# 02_MCU.net
KiCad netlist of a schematic drawn in Altium Designer
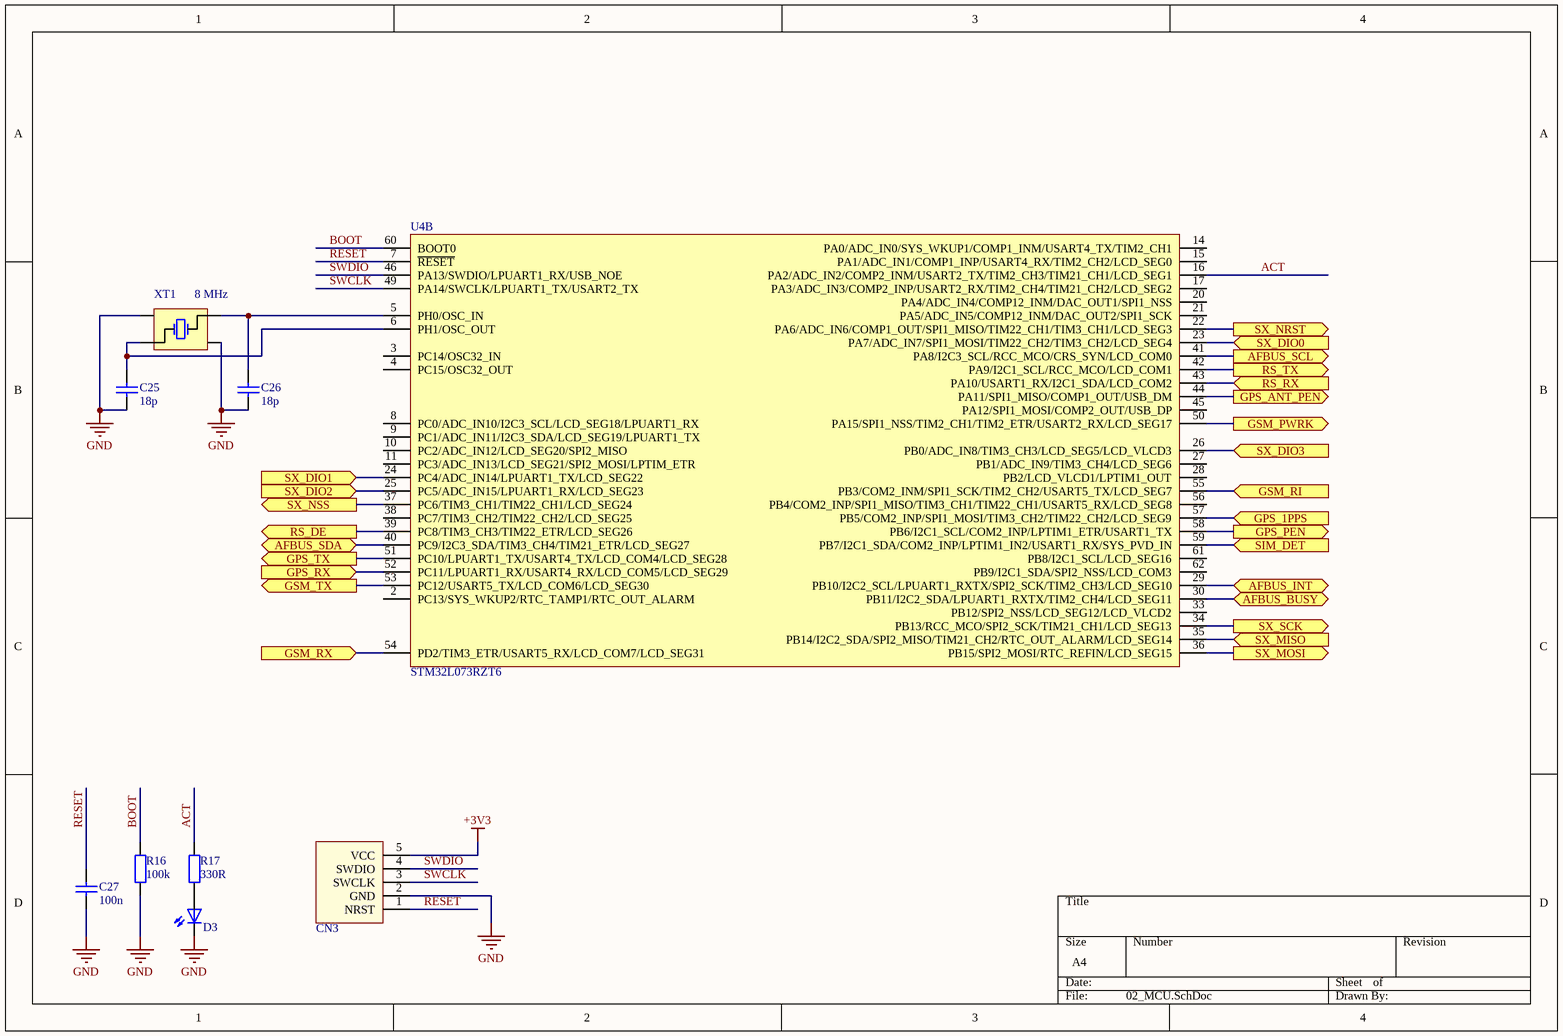
[diagram p0: 02_MCU.SchDoc]

(export (version "E")
  (design (tool "Eeschema 10.0.6"))
  (components
    (comp (ref "C25")
      (value "18p")
      (footprint "C0603_IPC_MD")
      (description "CAP CER 18PF 50V C0G/NP0 0603")
      (fields
        (field (name "MANUFACTURER") "Samsung Electro-Mechanics")
        (field (name "MANUFACTURER PART NUMBER") "CL10C180JB8NNNC")
      )
      (libsource (lib "alfasat_lib") (part "CL10C180JB8NNNC"))
    )
    (comp (ref "C26")
      (value "18p")
      (footprint "C0603_IPC_MD")
      (description "CAP CER 18PF 50V C0G/NP0 0603")
      (fields
        (field (name "MANUFACTURER") "Samsung Electro-Mechanics")
        (field (name "MANUFACTURER PART NUMBER") "CL10C180JB8NNNC")
      )
      (libsource (lib "alfasat_lib") (part "CL10C180JB8NNNC"))
    )
    (comp (ref "C27")
      (value "100n")
      (footprint "C0603_IPC_MD")
      (description "CAP CER 0.1UF 16V X7R 0603")
      (fields
        (field (name "MANUFACTURER") "Samsung Electro-Mechanics")
        (field (name "MANUFACTURER PART NUMBER") "CL10B104KO8WPNC")
      )
      (libsource (lib "alfasat_lib") (part "CL10B104KO8WPNC"))
    )
    (comp (ref "CN3")
      (value "SWD")
      (footprint "SWD_CON_VAR2")
      (description "SWDIO SWCLK VDD GND NRST")
      (libsource (lib "alfasat_parts_lib") (part "SWD-CONNECTOR_VAR1"))
    )
    (comp (ref "D3")
      (value "LTST-C190GKT")
      (footprint "LED_0603")
      (description "LED GREEN CLEAR CHIP SMD 0603")
      (fields (field (name "MANUFACTURER") "Lite-On Inc."))
      (libsource (lib "alfasat_lib") (part "LTST-C190GKT"))
    )
    (comp (ref "R16")
      (value "100k")
      (footprint "R0603_IPC_MD")
      (description "RES 100K OHM 1% 1/10W 0603")
      (fields
        (field (name "MANUFACTURER") "Bourns Inc.")
        (field (name "MANUFACTURER PART NUMBER") "RMCF0603FT100K")
      )
      (libsource (lib "alfasat_lib") (part "RMCF0603FT100K"))
    )
    (comp (ref "R17")
      (value "330R")
      (footprint "R0603_IPC_MD")
      (description "RES SMD 330 OHM 5% 1/10W 0603")
      (fields
        (field (name "MANUFACTURER") "Bourns Inc.")
        (field (name "MANUFACTURER PART NUMBER") "CR0603-JW-331ELF")
      )
      (libsource (lib "alfasat_lib") (part "CR0603-JW-331ELF"))
    )
    (comp (ref "U4")
      (value "STM32L073RZT6")
      (footprint "LQFP64_10X10MM")
      (description "Ultra-low-power 32-bit MCU ARM®-based Cortex®-M0+")
      (fields (field (name "MANUFACTURER") "ST"))
      (libsource (lib "alfasat_lib") (part "STM32L073RZT6"))
    )
    (comp (ref "XT1")
      (value "8 MHz")
      (footprint "5.0X3.2_4PAD_SMT")
      (description "8MHz ±10ppm Crystal 10pF 200 Ohms 4-SMD, No Lead")
      (fields
        (field (name "MANUFACTURER PART NUMBER") "ABM3B-8.000MHZ-10-1-U-T")
        (field (name "MANUFACTURER") "Abracon LLC")
      )
      (libsource (lib "alfasat_lib") (part "ABM3B-8.000MHZ-10-1-U-T"))
    )
  )
  (nets
    (net (code "1") (name "+3V3") (class "Default")
      (node (ref "CN3") (pin "5") (pinfunction "VCC_5") (pintype "passive"))
    )
    (net (code "2") (name "/ACT") (class "Default")
      (node (ref "R17") (pin "1") (pinfunction "1_1") (pintype "passive"))
      (node (ref "U4") (pin "16") (pinfunction "PA2/ADC_IN2/COMP2_INM/USART2_TX/TIM2_CH3/TIM21_CH1/LCD_SEG1_16") (pintype "passive"))
    )
    (net (code "3") (name "/AFBUS_BUSY") (class "Default")
      (node (ref "U4") (pin "30") (pinfunction "PB11/I2C2_SDA/LPUART1_RXTX/TIM2_CH4/LCD_SEG11_30") (pintype "passive"))
    )
    (net (code "4") (name "/AFBUS_INT") (class "Default")
      (node (ref "U4") (pin "29") (pinfunction "PB10/I2C2_SCL/LPUART1_RXTX/SPI2_SCK/TIM2_CH3/LCD_SEG10_29") (pintype "passive"))
    )
    (net (code "5") (name "/AFBUS_SCL") (class "Default")
      (node (ref "U4") (pin "41") (pinfunction "PA8/I2C3_SCL/RCC_MCO/CRS_SYN/LCD_COM0_41") (pintype "passive"))
    )
    (net (code "6") (name "/AFBUS_SDA") (class "Default")
      (node (ref "U4") (pin "40") (pinfunction "PC9/I2C3_SDA/TIM3_CH4/TIM21_ETR/LCD_SEG27_40") (pintype "passive"))
    )
    (net (code "7") (name "/BOOT") (class "Default")
      (node (ref "R16") (pin "2") (pinfunction "2_2") (pintype "passive"))
      (node (ref "U4") (pin "60") (pinfunction "BOOT0_60") (pintype "passive"))
    )
    (net (code "8") (name "/GPS_1PPS") (class "Default")
      (node (ref "U4") (pin "57") (pinfunction "PB5/COM2_INP/SPI1_MOSI/TIM3_CH2/TIM22_CH2/LCD_SEG9_57") (pintype "passive"))
    )
    (net (code "9") (name "/GPS_ANT_PEN") (class "Default")
      (node (ref "U4") (pin "44") (pinfunction "PA11/SPI1_MISO/COMP1_OUT/USB_DM_44") (pintype "passive"))
    )
    (net (code "10") (name "/GPS_PEN") (class "Default")
      (node (ref "U4") (pin "58") (pinfunction "PB6/I2C1_SCL/COM2_INP/LPTIM1_ETR/USART1_TX_58") (pintype "passive"))
    )
    (net (code "11") (name "/GPS_RX") (class "Default")
      (node (ref "U4") (pin "52") (pinfunction "PC11/LPUART1_RX/USART4_RX/LCD_COM5/LCD_SEG29_52") (pintype "passive"))
    )
    (net (code "12") (name "/GPS_TX") (class "Default")
      (node (ref "U4") (pin "51") (pinfunction "PC10/LPUART1_TX/USART4_TX/LCD_COM4/LCD_SEG28_51") (pintype "passive"))
    )
    (net (code "13") (name "/GSM_PWRK") (class "Default")
      (node (ref "U4") (pin "50") (pinfunction "PA15/SPI1_NSS/TIM2_CH1/TIM2_ETR/USART2_RX/LCD_SEG17_50") (pintype "passive"))
    )
    (net (code "14") (name "/GSM_RI") (class "Default")
      (node (ref "U4") (pin "55") (pinfunction "PB3/COM2_INM/SPI1_SCK/TIM2_CH2/USART5_TX/LCD_SEG7_55") (pintype "passive"))
    )
    (net (code "15") (name "/GSM_RX") (class "Default")
      (node (ref "U4") (pin "54") (pinfunction "PD2/TIM3_ETR/USART5_RX/LCD_COM7/LCD_SEG31_54") (pintype "passive"))
    )
    (net (code "16") (name "/GSM_TX") (class "Default")
      (node (ref "U4") (pin "53") (pinfunction "PC12/USART5_TX/LCD_COM6/LCD_SEG30_53") (pintype "passive"))
    )
    (net (code "17") (name "/RESET") (class "Default")
      (node (ref "C27") (pin "2") (pinfunction "2_2") (pintype "passive"))
      (node (ref "CN3") (pin "1") (pinfunction "NRST_1") (pintype "passive"))
      (node (ref "U4") (pin "7") (pinfunction "~{RESET}_7") (pintype "passive"))
    )
    (net (code "18") (name "/RS_DE") (class "Default")
      (node (ref "U4") (pin "39") (pinfunction "PC8/TIM3_CH3/TIM22_ETR/LCD_SEG26_39") (pintype "passive"))
    )
    (net (code "19") (name "/RS_RX") (class "Default")
      (node (ref "U4") (pin "43") (pinfunction "PA10/USART1_RX/I2C1_SDA/LCD_COM2_43") (pintype "passive"))
    )
    (net (code "20") (name "/RS_TX") (class "Default")
      (node (ref "U4") (pin "42") (pinfunction "PA9/I2C1_SCL/RCC_MCO/LCD_COM1_42") (pintype "passive"))
    )
    (net (code "21") (name "/SIM_DET") (class "Default")
      (node (ref "U4") (pin "59") (pinfunction "PB7/I2C1_SDA/COM2_INP/LPTIM1_IN2/USART1_RX/SYS_PVD_IN_59") (pintype "passive"))
    )
    (net (code "22") (name "/SWCLK") (class "Default")
      (node (ref "CN3") (pin "3") (pinfunction "SWCLK_3") (pintype "passive"))
      (node (ref "U4") (pin "49") (pinfunction "PA14/SWCLK/LPUART1_TX/USART2_TX_49") (pintype "passive"))
    )
    (net (code "23") (name "/SWDIO") (class "Default")
      (node (ref "CN3") (pin "4") (pinfunction "SWDIO_4") (pintype "passive"))
      (node (ref "U4") (pin "46") (pinfunction "PA13/SWDIO/LPUART1_RX/USB_NOE_46") (pintype "passive"))
    )
    (net (code "24") (name "/SX_DIO0") (class "Default")
      (node (ref "U4") (pin "23") (pinfunction "PA7/ADC_IN7/SPI1_MOSI/TIM22_CH2/TIM3_CH2/LCD_SEG4_23") (pintype "passive"))
    )
    (net (code "25") (name "/SX_DIO1") (class "Default")
      (node (ref "U4") (pin "24") (pinfunction "PC4/ADC_IN14/LPUART1_TX/LCD_SEG22_24") (pintype "passive"))
    )
    (net (code "26") (name "/SX_DIO2") (class "Default")
      (node (ref "U4") (pin "25") (pinfunction "PC5/ADC_IN15/LPUART1_RX/LCD_SEG23_25") (pintype "passive"))
    )
    (net (code "27") (name "/SX_DIO3") (class "Default")
      (node (ref "U4") (pin "26") (pinfunction "PB0/ADC_IN8/TIM3_CH3/LCD_SEG5/LCD_VLCD3_26") (pintype "passive"))
    )
    (net (code "28") (name "/SX_MISO") (class "Default")
      (node (ref "U4") (pin "35") (pinfunction "PB14/I2C2_SDA/SPI2_MISO/TIM21_CH2/RTC_OUT_ALARM/LCD_SEG14_35") (pintype "passive"))
    )
    (net (code "29") (name "/SX_MOSI") (class "Default")
      (node (ref "U4") (pin "36") (pinfunction "PB15/SPI2_MOSI/RTC_REFIN/LCD_SEG15_36") (pintype "passive"))
    )
    (net (code "30") (name "/SX_NRST") (class "Default")
      (node (ref "U4") (pin "22") (pinfunction "PA6/ADC_IN6/COMP1_OUT/SPI1_MISO/TIM22_CH1/TIM3_CH1/LCD_SEG3_22") (pintype "passive"))
    )
    (net (code "31") (name "/SX_NSS") (class "Default")
      (node (ref "U4") (pin "37") (pinfunction "PC6/TIM3_CH1/TIM22_CH1/LCD_SEG24_37") (pintype "passive"))
    )
    (net (code "32") (name "/SX_SCK") (class "Default")
      (node (ref "U4") (pin "34") (pinfunction "PB13/RCC_MCO/SPI2_SCK/TIM21_CH1/LCD_SEG13_34") (pintype "passive"))
    )
    (net (code "33") (name "GND") (class "Default")
      (node (ref "C25") (pin "1") (pinfunction "1_1") (pintype "passive"))
      (node (ref "C26") (pin "1") (pinfunction "1_1") (pintype "passive"))
      (node (ref "C27") (pin "1") (pinfunction "1_1") (pintype "passive"))
      (node (ref "CN3") (pin "2") (pinfunction "GND_2") (pintype "passive"))
      (node (ref "D3") (pin "1") (pinfunction "C_1") (pintype "passive"))
      (node (ref "R16") (pin "1") (pinfunction "1_1") (pintype "passive"))
      (node (ref "XT1") (pin "2") (pinfunction "NC_2") (pintype "passive"))
      (node (ref "XT1") (pin "4") (pinfunction "NC_4") (pintype "passive"))
    )
    (net (code "34") (name "Net-(D3-A)") (class "Default")
      (node (ref "D3") (pin "2") (pinfunction "A_2") (pintype "passive"))
      (node (ref "R17") (pin "2") (pinfunction "2_2") (pintype "passive"))
    )
    (net (code "35") (name "Net-(U4B-PH0{slash}OSC_IN)") (class "Default")
      (node (ref "C26") (pin "2") (pinfunction "2_2") (pintype "passive"))
      (node (ref "U4") (pin "5") (pinfunction "PH0/OSC_IN_5") (pintype "passive"))
      (node (ref "XT1") (pin "3") (pinfunction "OSC2_3") (pintype "passive"))
    )
    (net (code "36") (name "Net-(U4B-PH1{slash}OSC_OUT)") (class "Default")
      (node (ref "C25") (pin "2") (pinfunction "2_2") (pintype "passive"))
      (node (ref "U4") (pin "6") (pinfunction "PH1/OSC_OUT_6") (pintype "passive"))
      (node (ref "XT1") (pin "1") (pinfunction "OSC1_1") (pintype "passive"))
    )
    (net (code "37") (name "unconnected-(U4B-PA0{slash}ADC_IN0{slash}SYS_WKUP1{slash}COMP1_INM{slash}USART4_TX{slash}TIM2_CH1-Pad14)") (class "Default")
      (node (ref "U4") (pin "14") (pinfunction "PA0/ADC_IN0/SYS_WKUP1/COMP1_INM/USART4_TX/TIM2_CH1_14") (pintype "passive"))
    )
    (net (code "38") (name "unconnected-(U4B-PA1{slash}ADC_IN1{slash}COMP1_INP{slash}USART4_RX{slash}TIM2_CH2{slash}LCD_SEG0-Pad15)") (class "Default")
      (node (ref "U4") (pin "15") (pinfunction "PA1/ADC_IN1/COMP1_INP/USART4_RX/TIM2_CH2/LCD_SEG0_15") (pintype "passive"))
    )
    (net (code "39") (name "unconnected-(U4B-PA3{slash}ADC_IN3{slash}COMP2_INP{slash}USART2_RX{slash}TIM2_CH4{slash}TIM21_CH2{slash}LCD_SEG2-Pad17)") (class "Default")
      (node (ref "U4") (pin "17") (pinfunction "PA3/ADC_IN3/COMP2_INP/USART2_RX/TIM2_CH4/TIM21_CH2/LCD_SEG2_17") (pintype "passive"))
    )
    (net (code "40") (name "unconnected-(U4B-PA4{slash}ADC_IN4{slash}COMP12_INM{slash}DAC_OUT1{slash}SPI1_NSS-Pad20)") (class "Default")
      (node (ref "U4") (pin "20") (pinfunction "PA4/ADC_IN4/COMP12_INM/DAC_OUT1/SPI1_NSS_20") (pintype "passive"))
    )
    (net (code "41") (name "unconnected-(U4B-PA5{slash}ADC_IN5{slash}COMP12_INM{slash}DAC_OUT2{slash}SPI1_SCK-Pad21)") (class "Default")
      (node (ref "U4") (pin "21") (pinfunction "PA5/ADC_IN5/COMP12_INM/DAC_OUT2/SPI1_SCK_21") (pintype "passive"))
    )
    (net (code "42") (name "unconnected-(U4B-PA12{slash}SPI1_MOSI{slash}COMP2_OUT{slash}USB_DP-Pad45)") (class "Default")
      (node (ref "U4") (pin "45") (pinfunction "PA12/SPI1_MOSI/COMP2_OUT/USB_DP_45") (pintype "passive"))
    )
    (net (code "43") (name "unconnected-(U4B-PB1{slash}ADC_IN9{slash}TIM3_CH4{slash}LCD_SEG6-Pad27)") (class "Default")
      (node (ref "U4") (pin "27") (pinfunction "PB1/ADC_IN9/TIM3_CH4/LCD_SEG6_27") (pintype "passive"))
    )
    (net (code "44") (name "unconnected-(U4B-PB2{slash}LCD_VLCD1{slash}LPTIM1_OUT-Pad28)") (class "Default")
      (node (ref "U4") (pin "28") (pinfunction "PB2/LCD_VLCD1/LPTIM1_OUT_28") (pintype "passive"))
    )
    (net (code "45") (name "unconnected-(U4B-PB4{slash}COM2_INP{slash}SPI1_MISO{slash}TIM3_CH1{slash}TIM22_CH1{slash}USART5_RX{slash}LCD_SEG8-Pad56)") (class "Default")
      (node (ref "U4") (pin "56") (pinfunction "PB4/COM2_INP/SPI1_MISO/TIM3_CH1/TIM22_CH1/USART5_RX/LCD_SEG8_56") (pintype "passive"))
    )
    (net (code "46") (name "unconnected-(U4B-PB8{slash}I2C1_SCL{slash}LCD_SEG16-Pad61)") (class "Default")
      (node (ref "U4") (pin "61") (pinfunction "PB8/I2C1_SCL/LCD_SEG16_61") (pintype "passive"))
    )
    (net (code "47") (name "unconnected-(U4B-PB9{slash}I2C1_SDA{slash}SPI2_NSS{slash}LCD_COM3-Pad62)") (class "Default")
      (node (ref "U4") (pin "62") (pinfunction "PB9/I2C1_SDA/SPI2_NSS/LCD_COM3_62") (pintype "passive"))
    )
    (net (code "48") (name "unconnected-(U4B-PB12{slash}SPI2_NSS{slash}LCD_SEG12{slash}LCD_VLCD2-Pad33)") (class "Default")
      (node (ref "U4") (pin "33") (pinfunction "PB12/SPI2_NSS/LCD_SEG12/LCD_VLCD2_33") (pintype "passive"))
    )
    (net (code "49") (name "unconnected-(U4B-PC0{slash}ADC_IN10{slash}I2C3_SCL{slash}LCD_SEG18{slash}LPUART1_RX-Pad8)") (class "Default")
      (node (ref "U4") (pin "8") (pinfunction "PC0/ADC_IN10/I2C3_SCL/LCD_SEG18/LPUART1_RX_8") (pintype "passive"))
    )
    (net (code "50") (name "unconnected-(U4B-PC1{slash}ADC_IN11{slash}I2C3_SDA{slash}LCD_SEG19{slash}LPUART1_TX-Pad9)") (class "Default")
      (node (ref "U4") (pin "9") (pinfunction "PC1/ADC_IN11/I2C3_SDA/LCD_SEG19/LPUART1_TX_9") (pintype "passive"))
    )
    (net (code "51") (name "unconnected-(U4B-PC2{slash}ADC_IN12{slash}LCD_SEG20{slash}SPI2_MISO-Pad10)") (class "Default")
      (node (ref "U4") (pin "10") (pinfunction "PC2/ADC_IN12/LCD_SEG20/SPI2_MISO_10") (pintype "passive"))
    )
    (net (code "52") (name "unconnected-(U4B-PC3{slash}ADC_IN13{slash}LCD_SEG21{slash}SPI2_MOSI{slash}LPTIM_ETR-Pad11)") (class "Default")
      (node (ref "U4") (pin "11") (pinfunction "PC3/ADC_IN13/LCD_SEG21/SPI2_MOSI/LPTIM_ETR_11") (pintype "passive"))
    )
    (net (code "53") (name "unconnected-(U4B-PC7{slash}TIM3_CH2{slash}TIM22_CH2{slash}LCD_SEG25-Pad38)") (class "Default")
      (node (ref "U4") (pin "38") (pinfunction "PC7/TIM3_CH2/TIM22_CH2/LCD_SEG25_38") (pintype "passive"))
    )
    (net (code "54") (name "unconnected-(U4B-PC13{slash}SYS_WKUP2{slash}RTC_TAMP1{slash}RTC_OUT_ALARM-Pad2)") (class "Default")
      (node (ref "U4") (pin "2") (pinfunction "PC13/SYS_WKUP2/RTC_TAMP1/RTC_OUT_ALARM_2") (pintype "passive"))
    )
    (net (code "55") (name "unconnected-(U4B-PC14{slash}OSC32_IN-Pad3)") (class "Default")
      (node (ref "U4") (pin "3") (pinfunction "PC14/OSC32_IN_3") (pintype "passive"))
    )
    (net (code "56") (name "unconnected-(U4B-PC15{slash}OSC32_OUT-Pad4)") (class "Default")
      (node (ref "U4") (pin "4") (pinfunction "PC15/OSC32_OUT_4") (pintype "passive"))
    )
  )
)
